# M715F.net
KiCad netlist of a schematic drawn in EAGLE
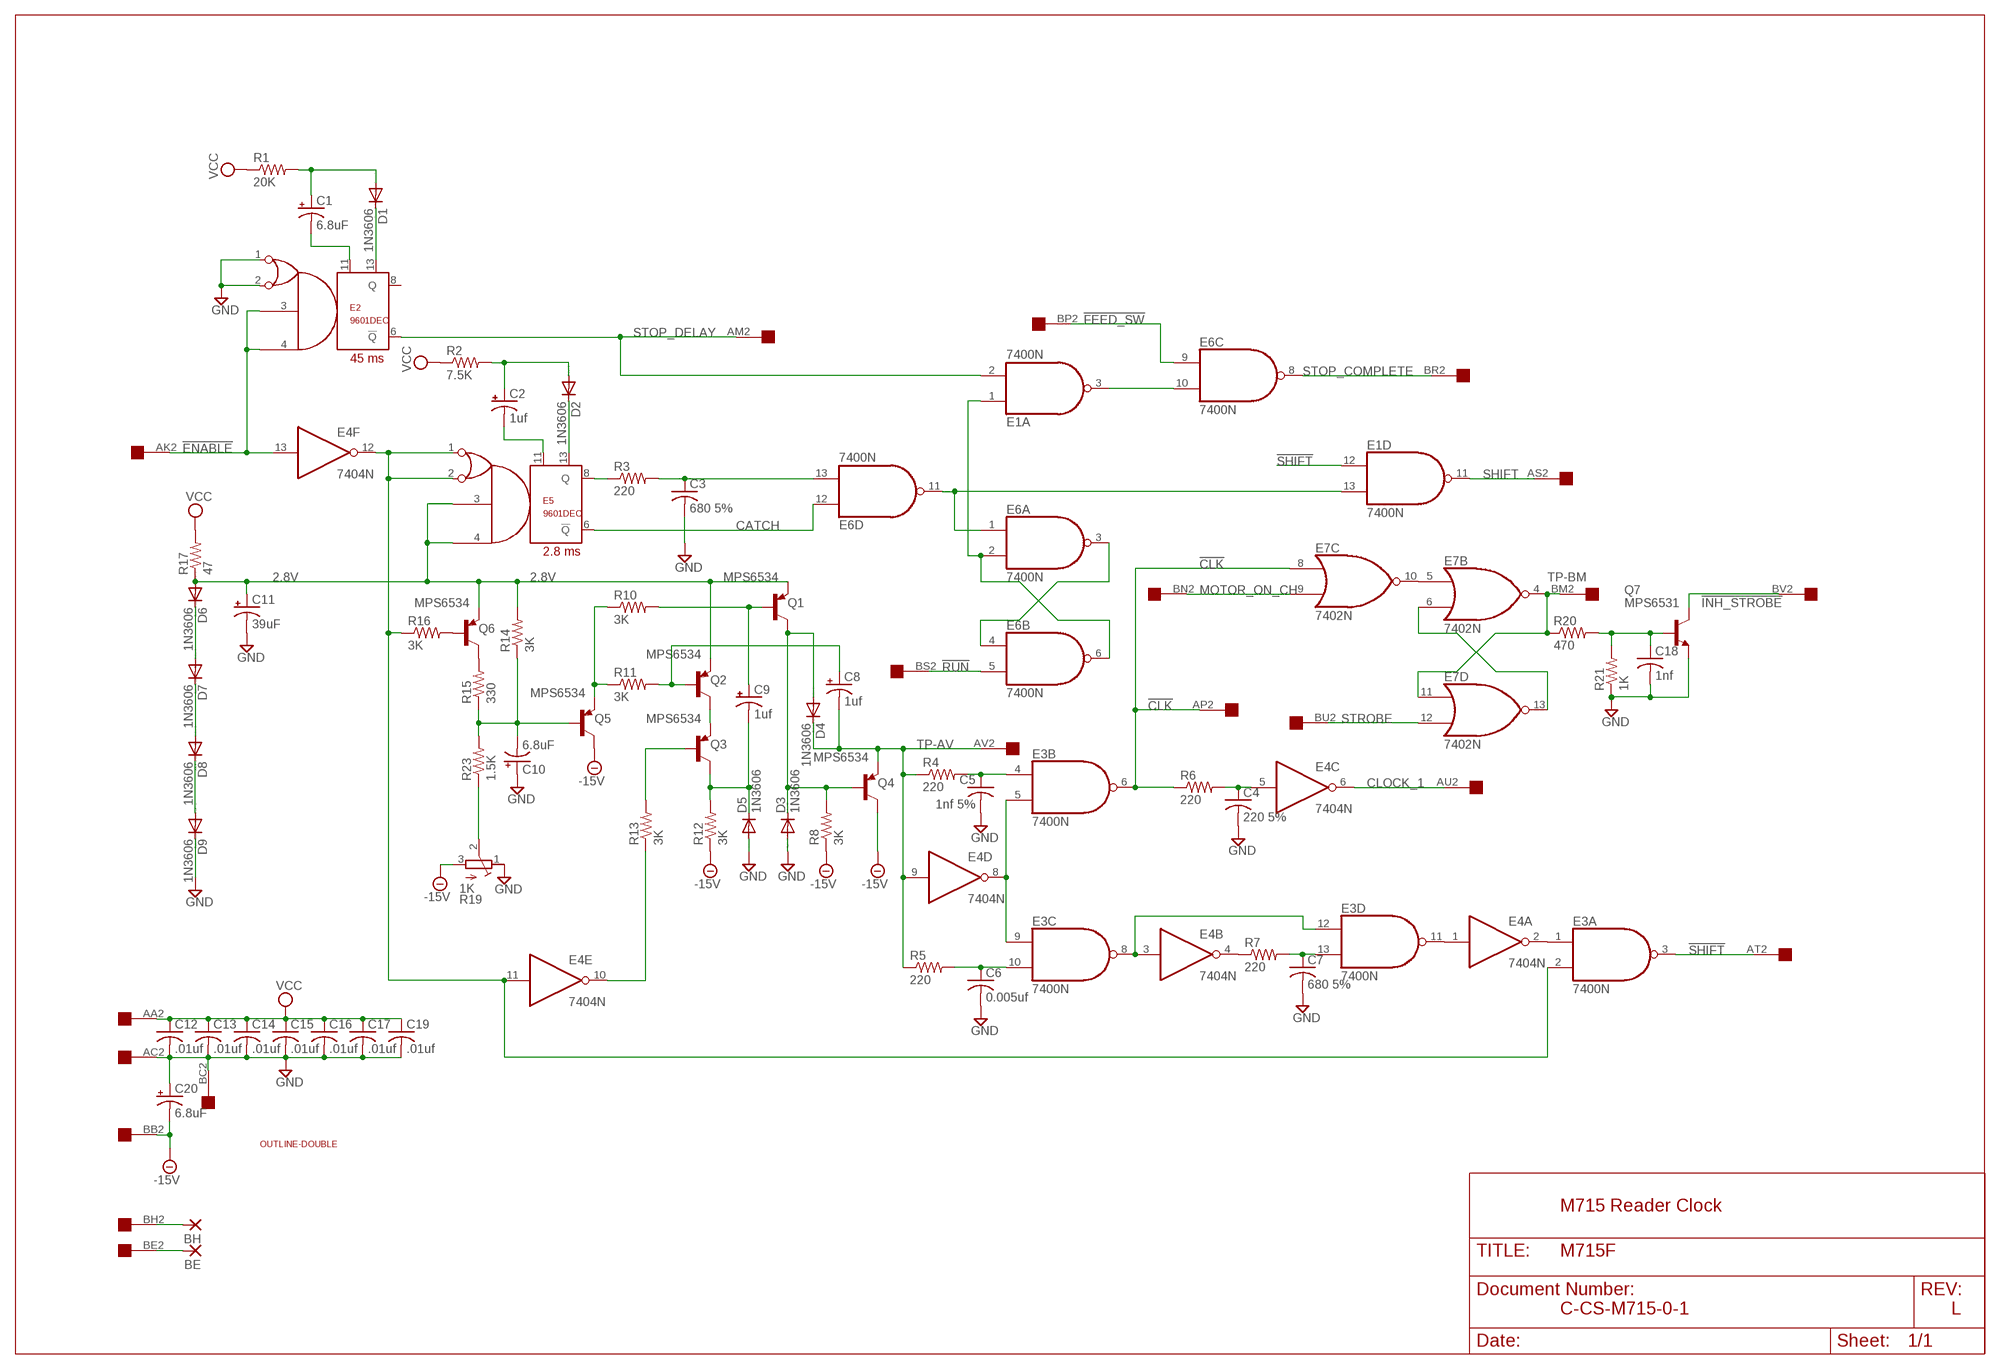
[diagram p0: schematic, sheet 1]

(export (version "E")
  (design (tool "Eeschema 10.0.6"))
  (components
    (comp (ref "BE")
      (value "1,6/0,8")
      (footprint "eagle-import:1,6_0,8")
      (libsource (lib "eagle-import") (part "1,6/0,8"))
    )
    (comp (ref "BH")
      (value "1,6/0,8")
      (footprint "eagle-import:1,6_0,8")
      (libsource (lib "eagle-import") (part "1,6/0,8"))
    )
    (comp (ref "C1")
      (value "6.8uF")
      (footprint "eagle-import:E12-8")
      (libsource (lib "eagle-import") (part "CPOL-USE20-8AXIAL"))
    )
    (comp (ref "C2")
      (value "1uf")
      (footprint "eagle-import:E15-5")
      (libsource (lib "eagle-import") (part "CPOL-USE15-5AXIAL"))
    )
    (comp (ref "C3")
      (value "680 5%")
      (footprint "eagle-import:C050-025X075")
      (libsource (lib "eagle-import") (part "C-US050-025X075"))
    )
    (comp (ref "C4")
      (value "220 5%")
      (footprint "eagle-import:C050-025X075")
      (libsource (lib "eagle-import") (part "C-US050-025X075"))
    )
    (comp (ref "C5")
      (value "1nf 5%")
      (footprint "eagle-import:C050-025X075")
      (libsource (lib "eagle-import") (part "C-US050-025X075"))
    )
    (comp (ref "C6")
      (value "0.005uf")
      (footprint "eagle-import:C050-025X075")
      (libsource (lib "eagle-import") (part "C-US050-025X075"))
    )
    (comp (ref "C7")
      (value "680 5%")
      (footprint "eagle-import:C050-025X075")
      (libsource (lib "eagle-import") (part "C-US050-025X075"))
    )
    (comp (ref "C8")
      (value "1uf")
      (footprint "eagle-import:E15-5")
      (libsource (lib "eagle-import") (part "CPOL-USE15-5AXIAL"))
    )
    (comp (ref "C9")
      (value "1uf")
      (footprint "eagle-import:E15-5")
      (libsource (lib "eagle-import") (part "CPOL-USE15-5AXIAL"))
    )
    (comp (ref "C10")
      (value "6.8uF")
      (footprint "eagle-import:E12-8")
      (libsource (lib "eagle-import") (part "CPOL-USE20-8AXIAL"))
    )
    (comp (ref "C11")
      (value "39uF")
      (footprint "eagle-import:E12-8")
      (libsource (lib "eagle-import") (part "CPOL-USE20-8AXIAL"))
    )
    (comp (ref "C12")
      (value ".01uf")
      (footprint "eagle-import:C050-025X075")
      (libsource (lib "eagle-import") (part "C-US050-025X075"))
    )
    (comp (ref "C13")
      (value ".01uf")
      (footprint "eagle-import:C050-025X075")
      (libsource (lib "eagle-import") (part "C-US050-025X075"))
    )
    (comp (ref "C14")
      (value ".01uf")
      (footprint "eagle-import:C050-025X075")
      (libsource (lib "eagle-import") (part "C-US050-025X075"))
    )
    (comp (ref "C15")
      (value ".01uf")
      (footprint "eagle-import:C050-025X075")
      (libsource (lib "eagle-import") (part "C-US050-025X075"))
    )
    (comp (ref "C16")
      (value ".01uf")
      (footprint "eagle-import:C050-025X075")
      (libsource (lib "eagle-import") (part "C-US050-025X075"))
    )
    (comp (ref "C17")
      (value ".01uf")
      (footprint "eagle-import:C050-025X075")
      (libsource (lib "eagle-import") (part "C-US050-025X075"))
    )
    (comp (ref "C18")
      (value "1nf")
      (footprint "eagle-import:C050-025X075")
      (libsource (lib "eagle-import") (part "C-US050-025X075"))
    )
    (comp (ref "C19")
      (value ".01uf")
      (footprint "eagle-import:C050-025X075")
      (libsource (lib "eagle-import") (part "C-US050-025X075"))
    )
    (comp (ref "C20")
      (value "6.8uF")
      (footprint "eagle-import:E12-8")
      (libsource (lib "eagle-import") (part "CPOL-USE20-8AXIAL"))
    )
    (comp (ref "D1")
      (value "1N3606")
      (footprint "eagle-import:DO35-10")
      (libsource (lib "eagle-import") (part "1N4148DO35-10"))
    )
    (comp (ref "D2")
      (value "1N3606")
      (footprint "eagle-import:DO35-10")
      (libsource (lib "eagle-import") (part "1N4148DO35-10"))
    )
    (comp (ref "D3")
      (value "1N3606")
      (footprint "eagle-import:DO35-10")
      (libsource (lib "eagle-import") (part "1N4148DO35-10"))
    )
    (comp (ref "D4")
      (value "1N3606")
      (footprint "eagle-import:DO35-10")
      (libsource (lib "eagle-import") (part "1N4148DO35-10"))
    )
    (comp (ref "D5")
      (value "1N3606")
      (footprint "eagle-import:DO35-10")
      (libsource (lib "eagle-import") (part "1N4148DO35-10"))
    )
    (comp (ref "D6")
      (value "1N3606")
      (footprint "eagle-import:DO35-10")
      (libsource (lib "eagle-import") (part "1N4148DO35-10"))
    )
    (comp (ref "D7")
      (value "1N3606")
      (footprint "eagle-import:DO35-10")
      (libsource (lib "eagle-import") (part "1N4148DO35-10"))
    )
    (comp (ref "D8")
      (value "1N3606")
      (footprint "eagle-import:DO35-10")
      (libsource (lib "eagle-import") (part "1N4148DO35-10"))
    )
    (comp (ref "D9")
      (value "1N3606")
      (footprint "eagle-import:DO35-10")
      (libsource (lib "eagle-import") (part "1N4148DO35-10"))
    )
    (comp (ref "E1")
      (value "7400N")
      (footprint "eagle-import:DIL14")
      (libsource (lib "eagle-import") (part "7400N"))
    )
    (comp (ref "E2")
      (value "9601DEC")
      (footprint "eagle-import:DIL14")
      (libsource (lib "eagle-import") (part "9601"))
    )
    (comp (ref "E3")
      (value "7400N")
      (footprint "eagle-import:DIL14")
      (libsource (lib "eagle-import") (part "7400N"))
    )
    (comp (ref "E4")
      (value "7404N")
      (footprint "eagle-import:DIL14")
      (libsource (lib "eagle-import") (part "7404N"))
    )
    (comp (ref "E5")
      (value "9601DEC")
      (footprint "eagle-import:DIL14")
      (libsource (lib "eagle-import") (part "9601"))
    )
    (comp (ref "E6")
      (value "7400N")
      (footprint "eagle-import:DIL14")
      (libsource (lib "eagle-import") (part "7400N"))
    )
    (comp (ref "E7")
      (value "7402N")
      (footprint "eagle-import:DIL14")
      (libsource (lib "eagle-import") (part "7402N"))
    )
    (comp (ref "Q1")
      (value "MPS6534")
      (footprint "eagle-import:TO5")
      (libsource (lib "eagle-import") (part "-PNP-TO5"))
    )
    (comp (ref "Q2")
      (value "MPS6534")
      (footprint "eagle-import:TO5")
      (libsource (lib "eagle-import") (part "-PNP-TO5"))
    )
    (comp (ref "Q3")
      (value "MPS6534")
      (footprint "eagle-import:TO5")
      (libsource (lib "eagle-import") (part "-PNP-TO5"))
    )
    (comp (ref "Q4")
      (value "MPS6534")
      (footprint "eagle-import:TO5")
      (libsource (lib "eagle-import") (part "-PNP-TO5"))
    )
    (comp (ref "Q5")
      (value "MPS6534")
      (footprint "eagle-import:TO5")
      (libsource (lib "eagle-import") (part "-PNP-TO5"))
    )
    (comp (ref "Q6")
      (value "MPS6534")
      (footprint "eagle-import:TO5")
      (libsource (lib "eagle-import") (part "-PNP-TO5"))
    )
    (comp (ref "Q7")
      (value "MPS6531")
      (footprint "eagle-import:TO5")
      (libsource (lib "eagle-import") (part "-NPN-TO5"))
    )
    (comp (ref "R1")
      (value "20K")
      (footprint "eagle-import:0207_10")
      (libsource (lib "eagle-import") (part "R-US_0207/10"))
    )
    (comp (ref "R2")
      (value "7.5K")
      (footprint "eagle-import:0207_10")
      (libsource (lib "eagle-import") (part "R-US_0207/10"))
    )
    (comp (ref "R3")
      (value "220")
      (footprint "eagle-import:0207_10")
      (libsource (lib "eagle-import") (part "R-US_0207/10"))
    )
    (comp (ref "R4")
      (value "220")
      (footprint "eagle-import:0207_10")
      (libsource (lib "eagle-import") (part "R-US_0207/10"))
    )
    (comp (ref "R5")
      (value "220")
      (footprint "eagle-import:0207_10")
      (libsource (lib "eagle-import") (part "R-US_0207/10"))
    )
    (comp (ref "R6")
      (value "220")
      (footprint "eagle-import:0207_10")
      (libsource (lib "eagle-import") (part "R-US_0207/10"))
    )
    (comp (ref "R7")
      (value "220")
      (footprint "eagle-import:0207_10")
      (libsource (lib "eagle-import") (part "R-US_0207/10"))
    )
    (comp (ref "R8")
      (value "3K")
      (footprint "eagle-import:0207_10")
      (libsource (lib "eagle-import") (part "R-US_0207/10"))
    )
    (comp (ref "R10")
      (value "3K")
      (footprint "eagle-import:0207_10")
      (libsource (lib "eagle-import") (part "R-US_0207/10"))
    )
    (comp (ref "R11")
      (value "3K")
      (footprint "eagle-import:0207_10")
      (libsource (lib "eagle-import") (part "R-US_0207/10"))
    )
    (comp (ref "R12")
      (value "3K")
      (footprint "eagle-import:0207_10")
      (libsource (lib "eagle-import") (part "R-US_0207/10"))
    )
    (comp (ref "R13")
      (value "3K")
      (footprint "eagle-import:0207_10")
      (libsource (lib "eagle-import") (part "R-US_0207/10"))
    )
    (comp (ref "R14")
      (value "3K")
      (footprint "eagle-import:0207_10")
      (libsource (lib "eagle-import") (part "R-US_0207/10"))
    )
    (comp (ref "R15")
      (value "330")
      (footprint "eagle-import:0207_10")
      (libsource (lib "eagle-import") (part "R-US_0207/10"))
    )
    (comp (ref "R16")
      (value "3K")
      (footprint "eagle-import:0207_10")
      (libsource (lib "eagle-import") (part "R-US_0207/10"))
    )
    (comp (ref "R17")
      (value "47")
      (footprint "eagle-import:0207_10")
      (libsource (lib "eagle-import") (part "R-US_0207/10"))
    )
    (comp (ref "R19")
      (value "1K")
      (footprint "eagle-import:3006Y")
      (libsource (lib "eagle-import") (part "275P"))
    )
    (comp (ref "R20")
      (value "470")
      (footprint "eagle-import:0207_10")
      (libsource (lib "eagle-import") (part "R-US_0207/10"))
    )
    (comp (ref "R21")
      (value "1K")
      (footprint "eagle-import:0207_10")
      (libsource (lib "eagle-import") (part "R-US_0207/10"))
    )
    (comp (ref "R23")
      (value "1.5K")
      (footprint "eagle-import:0207_10")
      (libsource (lib "eagle-import") (part "R-US_0207/10"))
    )
    (comp (ref "U$1")
      (value "DOUBLE")
      (footprint "eagle-import:EDGE-CON4")
      (libsource (lib "eagle-import") (part "DOUBLE"))
    )
    (comp (ref "U$2")
      (value "OUTLINE-DOUBLE")
      (footprint "eagle-import:DOUBLE")
      (libsource (lib "eagle-import") (part "OUTLINE-DOUBLE"))
    )
  )
  (nets
    (net (code "1") (name "-15V") (class "Default")
      (node (ref "C20") (pin "-") (pinfunction "-_-") (pintype "passive"))
      (node (ref "Q4") (pin "3") (pinfunction "C_3") (pintype "passive"))
      (node (ref "Q5") (pin "3") (pinfunction "C_3") (pintype "passive"))
      (node (ref "R12") (pin "1") (pinfunction "1_1") (pintype "passive"))
      (node (ref "R19") (pin "3") (pinfunction "E_3") (pintype "passive"))
      (node (ref "R8") (pin "1") (pinfunction "1_1") (pintype "passive"))
      (node (ref "U$1") (pin "BB2") (pinfunction "1_BB2") (pintype "bidirectional"))
    )
    (net (code "2") (name "/2.8V") (class "Default")
      (node (ref "C11") (pin "+") (pinfunction "+_+") (pintype "passive"))
      (node (ref "D6") (pin "A") (pinfunction "A_A") (pintype "passive"))
      (node (ref "E5") (pin "3") (pinfunction "P$3_3") (pintype "input"))
      (node (ref "E5") (pin "4") (pinfunction "P$4_4") (pintype "input"))
      (node (ref "Q1") (pin "1") (pinfunction "E_1") (pintype "passive"))
      (node (ref "Q2") (pin "1") (pinfunction "E_1") (pintype "passive"))
      (node (ref "Q6") (pin "1") (pinfunction "E_1") (pintype "passive"))
      (node (ref "R14") (pin "2") (pinfunction "2_2") (pintype "passive"))
      (node (ref "R17") (pin "1") (pinfunction "1_1") (pintype "passive"))
    )
    (net (code "3") (name "/CATCH") (class "Default")
      (node (ref "E5") (pin "6") (pinfunction "~{Q}_6") (pintype "output"))
      (node (ref "E6") (pin "12") (pinfunction "I0_12") (pintype "input"))
    )
    (net (code "4") (name "/CLOCK_1") (class "Default")
      (node (ref "E4") (pin "6") (pinfunction "O_6") (pintype "output"))
      (node (ref "U$1") (pin "AU2") (pinfunction "1_AU2") (pintype "bidirectional"))
    )
    (net (code "5") (name "/MOTOR_ON_CH") (class "Default")
      (node (ref "E7") (pin "9") (pinfunction "I1_9") (pintype "input"))
      (node (ref "U$1") (pin "BN2") (pinfunction "1_BN2") (pintype "bidirectional"))
    )
    (net (code "6") (name "/SHIFT") (class "Default")
      (node (ref "E1") (pin "11") (pinfunction "O_11") (pintype "output"))
      (node (ref "U$1") (pin "AS2") (pinfunction "1_AS2") (pintype "bidirectional"))
    )
    (net (code "7") (name "/STOP_COMPLETE") (class "Default")
      (node (ref "E6") (pin "8") (pinfunction "O_8") (pintype "output"))
      (node (ref "U$1") (pin "BR2") (pinfunction "1_BR2") (pintype "bidirectional"))
    )
    (net (code "8") (name "/STOP_DELAY") (class "Default")
      (node (ref "E1") (pin "2") (pinfunction "I1_2") (pintype "input"))
      (node (ref "E2") (pin "6") (pinfunction "~{Q}_6") (pintype "output"))
      (node (ref "U$1") (pin "AM2") (pinfunction "1_AM2") (pintype "bidirectional"))
    )
    (net (code "9") (name "/STROBE") (class "Default")
      (node (ref "E7") (pin "12") (pinfunction "I1_12") (pintype "input"))
      (node (ref "U$1") (pin "BU2") (pinfunction "1_BU2") (pintype "bidirectional"))
    )
    (net (code "10") (name "/TP-AV") (class "Default")
      (node (ref "C8") (pin "-") (pinfunction "-_-") (pintype "passive"))
      (node (ref "D4") (pin "C") (pinfunction "C_C") (pintype "passive"))
      (node (ref "E4") (pin "9") (pinfunction "I_9") (pintype "input"))
      (node (ref "Q4") (pin "1") (pinfunction "E_1") (pintype "passive"))
      (node (ref "R4") (pin "1") (pinfunction "1_1") (pintype "passive"))
      (node (ref "R5") (pin "1") (pinfunction "1_1") (pintype "passive"))
      (node (ref "U$1") (pin "AV2") (pinfunction "1_AV2") (pintype "bidirectional"))
    )
    (net (code "11") (name "/TP-BM") (class "Default")
      (node (ref "E7") (pin "11") (pinfunction "I0_11") (pintype "input"))
      (node (ref "E7") (pin "4") (pinfunction "O_4") (pintype "output"))
      (node (ref "R20") (pin "1") (pinfunction "1_1") (pintype "passive"))
      (node (ref "U$1") (pin "BM2") (pinfunction "1_BM2") (pintype "bidirectional"))
    )
    (net (code "12") (name "/~{CLK}") (class "Default")
      (node (ref "E3") (pin "6") (pinfunction "O_6") (pintype "output"))
      (node (ref "E7") (pin "8") (pinfunction "I0_8") (pintype "input"))
      (node (ref "R6") (pin "1") (pinfunction "1_1") (pintype "passive"))
      (node (ref "U$1") (pin "AP2") (pinfunction "1_AP2") (pintype "bidirectional"))
    )
    (net (code "13") (name "/~{ENABLE}") (class "Default")
      (node (ref "E2") (pin "3") (pinfunction "P$3_3") (pintype "input"))
      (node (ref "E2") (pin "4") (pinfunction "P$4_4") (pintype "input"))
      (node (ref "E4") (pin "13") (pinfunction "I_13") (pintype "input"))
      (node (ref "U$1") (pin "AK2") (pinfunction "1_AK2") (pintype "bidirectional"))
    )
    (net (code "14") (name "/~{FEED_SW}") (class "Default")
      (node (ref "E6") (pin "9") (pinfunction "I0_9") (pintype "input"))
      (node (ref "U$1") (pin "BP2") (pinfunction "1_BP2") (pintype "bidirectional"))
    )
    (net (code "15") (name "/~{INH_STROBE}") (class "Default")
      (node (ref "Q7") (pin "3") (pinfunction "C_3") (pintype "passive"))
      (node (ref "U$1") (pin "BV2") (pinfunction "1_BV2") (pintype "bidirectional"))
    )
    (net (code "16") (name "/~{RUN}") (class "Default")
      (node (ref "E6") (pin "5") (pinfunction "I1_5") (pintype "input"))
      (node (ref "U$1") (pin "BS2") (pinfunction "1_BS2") (pintype "bidirectional"))
    )
    (net (code "17") (name "/~{SHIFT}") (class "Default")
      (node (ref "E1") (pin "12") (pinfunction "I0_12") (pintype "input"))
      (node (ref "E3") (pin "3") (pinfunction "O_3") (pintype "output"))
      (node (ref "U$1") (pin "AT2") (pinfunction "1_AT2") (pintype "bidirectional"))
    )
    (net (code "18") (name "GND") (class "Default")
      (node (ref "C10") (pin "+") (pinfunction "+_+") (pintype "passive"))
      (node (ref "C11") (pin "-") (pinfunction "-_-") (pintype "passive"))
      (node (ref "C12") (pin "2") (pinfunction "2_2") (pintype "passive"))
      (node (ref "C13") (pin "2") (pinfunction "2_2") (pintype "passive"))
      (node (ref "C14") (pin "2") (pinfunction "2_2") (pintype "passive"))
      (node (ref "C15") (pin "2") (pinfunction "2_2") (pintype "passive"))
      (node (ref "C16") (pin "2") (pinfunction "2_2") (pintype "passive"))
      (node (ref "C17") (pin "2") (pinfunction "2_2") (pintype "passive"))
      (node (ref "C18") (pin "2") (pinfunction "2_2") (pintype "passive"))
      (node (ref "C19") (pin "2") (pinfunction "2_2") (pintype "passive"))
      (node (ref "C20") (pin "+") (pinfunction "+_+") (pintype "passive"))
      (node (ref "C3") (pin "2") (pinfunction "2_2") (pintype "passive"))
      (node (ref "C4") (pin "2") (pinfunction "2_2") (pintype "passive"))
      (node (ref "C5") (pin "2") (pinfunction "2_2") (pintype "passive"))
      (node (ref "C6") (pin "2") (pinfunction "2_2") (pintype "passive"))
      (node (ref "C7") (pin "2") (pinfunction "2_2") (pintype "passive"))
      (node (ref "D3") (pin "A") (pinfunction "A_A") (pintype "passive"))
      (node (ref "D5") (pin "A") (pinfunction "A_A") (pintype "passive"))
      (node (ref "D9") (pin "C") (pinfunction "C_C") (pintype "passive"))
      (node (ref "E2") (pin "1") (pinfunction "P$1_1") (pintype "input"))
      (node (ref "E2") (pin "2") (pinfunction "P$2_2") (pintype "input"))
      (node (ref "Q7") (pin "1") (pinfunction "E_1") (pintype "passive"))
      (node (ref "R19") (pin "1") (pinfunction "A_1") (pintype "passive"))
      (node (ref "R21") (pin "1") (pinfunction "1_1") (pintype "passive"))
      (node (ref "U$1") (pin "AC2") (pinfunction "1_AC2") (pintype "bidirectional"))
      (node (ref "U$1") (pin "BC2") (pinfunction "1_BC2") (pintype "bidirectional"))
    )
    (net (code "19") (name "Net-(BE-P)") (class "Default")
      (node (ref "BE") (pin "1") (pinfunction "P_1") (pintype "passive"))
      (node (ref "U$1") (pin "BE2") (pinfunction "1_BE2") (pintype "bidirectional"))
    )
    (net (code "20") (name "Net-(BH-P)") (class "Default")
      (node (ref "BH") (pin "1") (pinfunction "P_1") (pintype "passive"))
      (node (ref "U$1") (pin "BH2") (pinfunction "1_BH2") (pintype "bidirectional"))
    )
    (net (code "21") (name "Net-(C1-Pad+)") (class "Default")
      (node (ref "C1") (pin "+") (pinfunction "+_+") (pintype "passive"))
      (node (ref "D1") (pin "A") (pinfunction "A_A") (pintype "passive"))
      (node (ref "R1") (pin "2") (pinfunction "2_2") (pintype "passive"))
    )
    (net (code "22") (name "Net-(C2-Pad+)") (class "Default")
      (node (ref "C2") (pin "+") (pinfunction "+_+") (pintype "passive"))
      (node (ref "D2") (pin "A") (pinfunction "A_A") (pintype "passive"))
      (node (ref "R2") (pin "2") (pinfunction "2_2") (pintype "passive"))
    )
    (net (code "23") (name "Net-(D6-PadC)") (class "Default")
      (node (ref "D6") (pin "C") (pinfunction "C_C") (pintype "passive"))
      (node (ref "D7") (pin "A") (pinfunction "A_A") (pintype "passive"))
    )
    (net (code "24") (name "Net-(D7-PadC)") (class "Default")
      (node (ref "D7") (pin "C") (pinfunction "C_C") (pintype "passive"))
      (node (ref "D8") (pin "A") (pinfunction "A_A") (pintype "passive"))
    )
    (net (code "25") (name "Net-(D8-PadC)") (class "Default")
      (node (ref "D8") (pin "C") (pinfunction "C_C") (pintype "passive"))
      (node (ref "D9") (pin "A") (pinfunction "A_A") (pintype "passive"))
    )
    (net (code "26") (name "Net-(E1A-I0)") (class "Default")
      (node (ref "E1") (pin "1") (pinfunction "I0_1") (pintype "input"))
      (node (ref "E6") (pin "2") (pinfunction "I1_2") (pintype "input"))
      (node (ref "E6") (pin "6") (pinfunction "O_6") (pintype "output"))
    )
    (net (code "27") (name "Net-(E1A-O)") (class "Default")
      (node (ref "E1") (pin "3") (pinfunction "O_3") (pintype "output"))
      (node (ref "E6") (pin "10") (pinfunction "I1_10") (pintype "input"))
    )
    (net (code "28") (name "Net-(E1D-I1)") (class "Default")
      (node (ref "E1") (pin "13") (pinfunction "I1_13") (pintype "input"))
      (node (ref "E6") (pin "1") (pinfunction "I0_1") (pintype "input"))
      (node (ref "E6") (pin "11") (pinfunction "O_11") (pintype "output"))
    )
    (net (code "29") (name "Net-(E2A-P$5)") (class "Default")
      (node (ref "C1") (pin "-") (pinfunction "-_-") (pintype "passive"))
      (node (ref "E2") (pin "11") (pinfunction "P$5_11") (pintype "bidirectional"))
    )
    (net (code "30") (name "Net-(E2A-P$6)") (class "Default")
      (node (ref "D1") (pin "C") (pinfunction "C_C") (pintype "passive"))
      (node (ref "E2") (pin "13") (pinfunction "P$6_13") (pintype "bidirectional"))
    )
    (net (code "31") (name "Net-(E3A-I0)") (class "Default")
      (node (ref "E3") (pin "1") (pinfunction "I0_1") (pintype "input"))
      (node (ref "E4") (pin "2") (pinfunction "O_2") (pintype "output"))
    )
    (net (code "32") (name "Net-(E3A-I1)") (class "Default")
      (node (ref "E3") (pin "2") (pinfunction "I1_2") (pintype "input"))
      (node (ref "E4") (pin "11") (pinfunction "I_11") (pintype "input"))
      (node (ref "E4") (pin "12") (pinfunction "O_12") (pintype "output"))
      (node (ref "E5") (pin "1") (pinfunction "P$1_1") (pintype "input"))
      (node (ref "E5") (pin "2") (pinfunction "P$2_2") (pintype "input"))
      (node (ref "R16") (pin "1") (pinfunction "1_1") (pintype "passive"))
    )
    (net (code "33") (name "Net-(E3B-I0)") (class "Default")
      (node (ref "C5") (pin "1") (pinfunction "1_1") (pintype "passive"))
      (node (ref "E3") (pin "4") (pinfunction "I0_4") (pintype "input"))
      (node (ref "R4") (pin "2") (pinfunction "2_2") (pintype "passive"))
    )
    (net (code "34") (name "Net-(E3B-I1)") (class "Default")
      (node (ref "E3") (pin "5") (pinfunction "I1_5") (pintype "input"))
      (node (ref "E3") (pin "9") (pinfunction "I0_9") (pintype "input"))
      (node (ref "E4") (pin "8") (pinfunction "O_8") (pintype "output"))
    )
    (net (code "35") (name "Net-(E3C-I1)") (class "Default")
      (node (ref "C6") (pin "1") (pinfunction "1_1") (pintype "passive"))
      (node (ref "E3") (pin "10") (pinfunction "I1_10") (pintype "input"))
      (node (ref "R5") (pin "2") (pinfunction "2_2") (pintype "passive"))
    )
    (net (code "36") (name "Net-(E3C-O)") (class "Default")
      (node (ref "E3") (pin "12") (pinfunction "I0_12") (pintype "input"))
      (node (ref "E3") (pin "8") (pinfunction "O_8") (pintype "output"))
      (node (ref "E4") (pin "3") (pinfunction "I_3") (pintype "input"))
    )
    (net (code "37") (name "Net-(E3D-I1)") (class "Default")
      (node (ref "C7") (pin "1") (pinfunction "1_1") (pintype "passive"))
      (node (ref "E3") (pin "13") (pinfunction "I1_13") (pintype "input"))
      (node (ref "R7") (pin "2") (pinfunction "2_2") (pintype "passive"))
    )
    (net (code "38") (name "Net-(E3D-O)") (class "Default")
      (node (ref "E3") (pin "11") (pinfunction "O_11") (pintype "output"))
      (node (ref "E4") (pin "1") (pinfunction "I_1") (pintype "input"))
    )
    (net (code "39") (name "Net-(E4B-O)") (class "Default")
      (node (ref "E4") (pin "4") (pinfunction "O_4") (pintype "output"))
      (node (ref "R7") (pin "1") (pinfunction "1_1") (pintype "passive"))
    )
    (net (code "40") (name "Net-(E4C-I)") (class "Default")
      (node (ref "C4") (pin "1") (pinfunction "1_1") (pintype "passive"))
      (node (ref "E4") (pin "5") (pinfunction "I_5") (pintype "input"))
      (node (ref "R6") (pin "2") (pinfunction "2_2") (pintype "passive"))
    )
    (net (code "41") (name "Net-(E4E-O)") (class "Default")
      (node (ref "E4") (pin "10") (pinfunction "O_10") (pintype "output"))
      (node (ref "R13") (pin "1") (pinfunction "1_1") (pintype "passive"))
    )
    (net (code "42") (name "Net-(E5A-P$5)") (class "Default")
      (node (ref "C2") (pin "-") (pinfunction "-_-") (pintype "passive"))
      (node (ref "E5") (pin "11") (pinfunction "P$5_11") (pintype "bidirectional"))
    )
    (net (code "43") (name "Net-(E5A-P$6)") (class "Default")
      (node (ref "D2") (pin "C") (pinfunction "C_C") (pintype "passive"))
      (node (ref "E5") (pin "13") (pinfunction "P$6_13") (pintype "bidirectional"))
    )
    (net (code "44") (name "Net-(E5A-Q)") (class "Default")
      (node (ref "E5") (pin "8") (pinfunction "Q_8") (pintype "output"))
      (node (ref "R3") (pin "1") (pinfunction "1_1") (pintype "passive"))
    )
    (net (code "45") (name "Net-(E6A-O)") (class "Default")
      (node (ref "E6") (pin "3") (pinfunction "O_3") (pintype "output"))
      (node (ref "E6") (pin "4") (pinfunction "I0_4") (pintype "input"))
    )
    (net (code "46") (name "Net-(E6D-I1)") (class "Default")
      (node (ref "C3") (pin "1") (pinfunction "1_1") (pintype "passive"))
      (node (ref "E6") (pin "13") (pinfunction "I1_13") (pintype "input"))
      (node (ref "R3") (pin "2") (pinfunction "2_2") (pintype "passive"))
    )
    (net (code "47") (name "Net-(E7B-I0)") (class "Default")
      (node (ref "E7") (pin "10") (pinfunction "O_10") (pintype "output"))
      (node (ref "E7") (pin "5") (pinfunction "I0_5") (pintype "input"))
    )
    (net (code "48") (name "Net-(E7B-I1)") (class "Default")
      (node (ref "E7") (pin "13") (pinfunction "O_13") (pintype "output"))
      (node (ref "E7") (pin "6") (pinfunction "I1_6") (pintype "input"))
    )
    (net (code "49") (name "Net-(Q1-B)") (class "Default")
      (node (ref "C9") (pin "+") (pinfunction "+_+") (pintype "passive"))
      (node (ref "Q1") (pin "2") (pinfunction "B_2") (pintype "passive"))
      (node (ref "R10") (pin "2") (pinfunction "2_2") (pintype "passive"))
    )
    (net (code "50") (name "Net-(Q1-C)") (class "Default")
      (node (ref "D3") (pin "C") (pinfunction "C_C") (pintype "passive"))
      (node (ref "D4") (pin "A") (pinfunction "A_A") (pintype "passive"))
      (node (ref "Q1") (pin "3") (pinfunction "C_3") (pintype "passive"))
      (node (ref "Q4") (pin "2") (pinfunction "B_2") (pintype "passive"))
      (node (ref "R8") (pin "2") (pinfunction "2_2") (pintype "passive"))
    )
    (net (code "51") (name "Net-(Q2-B)") (class "Default")
      (node (ref "C8") (pin "+") (pinfunction "+_+") (pintype "passive"))
      (node (ref "Q2") (pin "2") (pinfunction "B_2") (pintype "passive"))
      (node (ref "R11") (pin "2") (pinfunction "2_2") (pintype "passive"))
    )
    (net (code "52") (name "Net-(Q2-C)") (class "Default")
      (node (ref "Q2") (pin "3") (pinfunction "C_3") (pintype "passive"))
      (node (ref "Q3") (pin "1") (pinfunction "E_1") (pintype "passive"))
    )
    (net (code "53") (name "Net-(Q3-B)") (class "Default")
      (node (ref "Q3") (pin "2") (pinfunction "B_2") (pintype "passive"))
      (node (ref "R13") (pin "2") (pinfunction "2_2") (pintype "passive"))
    )
    (net (code "54") (name "Net-(Q3-C)") (class "Default")
      (node (ref "C9") (pin "-") (pinfunction "-_-") (pintype "passive"))
      (node (ref "D5") (pin "C") (pinfunction "C_C") (pintype "passive"))
      (node (ref "Q3") (pin "3") (pinfunction "C_3") (pintype "passive"))
      (node (ref "R12") (pin "2") (pinfunction "2_2") (pintype "passive"))
    )
    (net (code "55") (name "Net-(Q5-B)") (class "Default")
      (node (ref "C10") (pin "-") (pinfunction "-_-") (pintype "passive"))
      (node (ref "Q5") (pin "2") (pinfunction "B_2") (pintype "passive"))
      (node (ref "R14") (pin "1") (pinfunction "1_1") (pintype "passive"))
      (node (ref "R15") (pin "1") (pinfunction "1_1") (pintype "passive"))
      (node (ref "R23") (pin "2") (pinfunction "2_2") (pintype "passive"))
    )
    (net (code "56") (name "Net-(Q5-E)") (class "Default")
      (node (ref "Q5") (pin "1") (pinfunction "E_1") (pintype "passive"))
      (node (ref "R10") (pin "1") (pinfunction "1_1") (pintype "passive"))
      (node (ref "R11") (pin "1") (pinfunction "1_1") (pintype "passive"))
    )
    (net (code "57") (name "Net-(Q6-B)") (class "Default")
      (node (ref "Q6") (pin "2") (pinfunction "B_2") (pintype "passive"))
      (node (ref "R16") (pin "2") (pinfunction "2_2") (pintype "passive"))
    )
    (net (code "58") (name "Net-(Q6-C)") (class "Default")
      (node (ref "Q6") (pin "3") (pinfunction "C_3") (pintype "passive"))
      (node (ref "R15") (pin "2") (pinfunction "2_2") (pintype "passive"))
    )
    (net (code "59") (name "Net-(Q7-B)") (class "Default")
      (node (ref "C18") (pin "1") (pinfunction "1_1") (pintype "passive"))
      (node (ref "Q7") (pin "2") (pinfunction "B_2") (pintype "passive"))
      (node (ref "R20") (pin "2") (pinfunction "2_2") (pintype "passive"))
      (node (ref "R21") (pin "2") (pinfunction "2_2") (pintype "passive"))
    )
    (net (code "60") (name "Net-(R19-S)") (class "Default")
      (node (ref "R19") (pin "2") (pinfunction "S_2") (pintype "passive"))
      (node (ref "R23") (pin "1") (pinfunction "1_1") (pintype "passive"))
    )
    (net (code "61") (name "VCC") (class "Default")
      (node (ref "C12") (pin "1") (pinfunction "1_1") (pintype "passive"))
      (node (ref "C13") (pin "1") (pinfunction "1_1") (pintype "passive"))
      (node (ref "C14") (pin "1") (pinfunction "1_1") (pintype "passive"))
      (node (ref "C15") (pin "1") (pinfunction "1_1") (pintype "passive"))
      (node (ref "C16") (pin "1") (pinfunction "1_1") (pintype "passive"))
      (node (ref "C17") (pin "1") (pinfunction "1_1") (pintype "passive"))
      (node (ref "C19") (pin "1") (pinfunction "1_1") (pintype "passive"))
      (node (ref "R1") (pin "1") (pinfunction "1_1") (pintype "passive"))
      (node (ref "R17") (pin "2") (pinfunction "2_2") (pintype "passive"))
      (node (ref "R2") (pin "1") (pinfunction "1_1") (pintype "passive"))
      (node (ref "U$1") (pin "AA2") (pinfunction "1_AA2") (pintype "bidirectional"))
    )
    (net (code "62") (name "unconnected-(E2A-Q-Pad8)") (class "Default")
      (node (ref "E2") (pin "8") (pinfunction "Q_8") (pintype "output"))
    )
  )
)
